# GPIO.net
KiCad netlist of a schematic drawn in Altium Designer
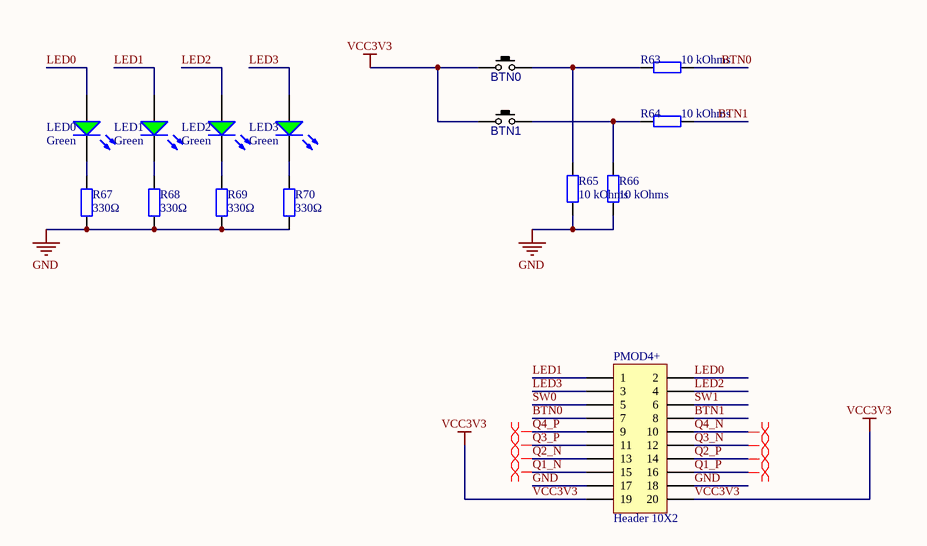
[diagram p0: GPIO.SchDoc]

(export (version "E")
  (design (tool "Eeschema 10.0.6"))
  (components
    (comp (ref "BTN0")
      (value "PUSHBUTTON")
      (footprint "SWPBS_SPST_6X3X5")
      (description "SWITCH, PUSH BUTTON, TACTILE, SMD, SPST, 6X3.5X4.3mm")
      (fields (field (name "MANF") "Panasonic") (field (name "MANF_P#") "EVQ-PNF04M"))
      (libsource (lib "Switch Push Botton") (part "SWPBS_SPST_6X3X4"))
    )
    (comp (ref "BTN1")
      (value "PUSHBUTTON")
      (footprint "SWPBS_SPST_6X3X5")
      (description "SWITCH, PUSH BUTTON, TACTILE, SMD, SPST, 6X3.5X4.3mm")
      (fields (field (name "MANF") "Panasonic") (field (name "MANF_P#") "EVQ-PNF04M"))
      (libsource (lib "Switch Push Botton") (part "SWPBS_SPST_6X3X4"))
    )
    (comp (ref "LED0")
      (value "Green")
      (footprint "0805_LED_S1")
      (description "发光二极管")
      (libsource (lib "LED") (part "0805 翠绿"))
    )
    (comp (ref "LED1")
      (value "Green")
      (footprint "0805_LED_S1")
      (description "发光二极管")
      (libsource (lib "LED") (part "0805 翠绿"))
    )
    (comp (ref "LED2")
      (value "Green")
      (footprint "0805_LED_S1")
      (description "发光二极管")
      (libsource (lib "LED") (part "0805 翠绿"))
    )
    (comp (ref "LED3")
      (value "Green")
      (footprint "0805_LED_S1")
      (description "发光二极管")
      (libsource (lib "LED") (part "0805 翠绿"))
    )
    (comp (ref "PMOD4+")
      (value "Header 10X2")
      (footprint "HDR2X10")
      (description "Header, 10-Pin, Dual row")
      (fields (field (name "PUBLISHER") "Altium Limited"))
      (libsource (lib "Miscellaneous Connectors") (part "Header 10X2"))
    )
    (comp (ref "R63")
      (value "10 kOhms")
      (footprint "RES0402i")
      (description "0402, 10K 1%,  62.5mW, 50V")
      (fields (field (name "PART NUMBER") "CR0402-FX-1002GLF") (field (name "VOLTAGE") "50V"))
      (libsource (lib "") (part "Res_10k_1%_0402_1"))
    )
    (comp (ref "R64")
      (value "10 kOhms")
      (footprint "RES0402i")
      (description "0402, 10K 1%,  62.5mW, 50V")
      (fields (field (name "PART NUMBER") "CR0402-FX-1002GLF") (field (name "VOLTAGE") "50V"))
      (libsource (lib "") (part "Res_10k_1%_0402_1"))
    )
    (comp (ref "R65")
      (value "10 kOhms")
      (footprint "RES0402i")
      (description "0402, 10K 1%,  62.5mW, 50V")
      (fields (field (name "PART NUMBER") "CR0402-FX-1002GLF") (field (name "VOLTAGE") "50V"))
      (libsource (lib "AmpherLib") (part "Res_10k_1%_0402"))
    )
    (comp (ref "R66")
      (value "10 kOhms")
      (footprint "RES0402i")
      (description "0402, 10K 1%,  62.5mW, 50V")
      (fields (field (name "PART NUMBER") "CR0402-FX-1002GLF") (field (name "VOLTAGE") "50V"))
      (libsource (lib "AmpherLib") (part "Res_10k_1%_0402"))
    )
    (comp (ref "R67")
      (value "330Ω")
      (footprint "0805_R")
      (description "贴片电阻")
      (libsource (lib "RES") (part "0805 330Ω (3300) 1%"))
    )
    (comp (ref "R68")
      (value "330Ω")
      (footprint "0805_R")
      (description "贴片电阻")
      (libsource (lib "RES") (part "0805 330Ω (3300) 1%"))
    )
    (comp (ref "R69")
      (value "330Ω")
      (footprint "0805_R")
      (description "贴片电阻")
      (libsource (lib "RES") (part "0805 330Ω (3300) 1%"))
    )
    (comp (ref "R70")
      (value "330Ω")
      (footprint "0805_R")
      (description "贴片电阻")
      (libsource (lib "RES") (part "0805 330Ω (3300) 1%"))
    )
  )
  (nets
    (net (code "1") (name "/BTN0") (class "Default")
      (node (ref "PMOD4+") (pin "7") (pinfunction "7_7") (pintype "passive"))
      (node (ref "R63") (pin "2") (pinfunction "2_2") (pintype "passive"))
    )
    (net (code "2") (name "/BTN1") (class "Default")
      (node (ref "PMOD4+") (pin "8") (pinfunction "8_8") (pintype "passive"))
      (node (ref "R64") (pin "2") (pinfunction "2_2") (pintype "passive"))
    )
    (net (code "3") (name "/LED0") (class "Default")
      (node (ref "LED0") (pin "A") (pinfunction "A_A") (pintype "passive"))
      (node (ref "PMOD4+") (pin "2") (pinfunction "2_2") (pintype "passive"))
    )
    (net (code "4") (name "/LED1") (class "Default")
      (node (ref "LED1") (pin "A") (pinfunction "A_A") (pintype "passive"))
      (node (ref "PMOD4+") (pin "1") (pinfunction "1_1") (pintype "passive"))
    )
    (net (code "5") (name "/LED2") (class "Default")
      (node (ref "LED2") (pin "A") (pinfunction "A_A") (pintype "passive"))
      (node (ref "PMOD4+") (pin "4") (pinfunction "4_4") (pintype "passive"))
    )
    (net (code "6") (name "/LED3") (class "Default")
      (node (ref "LED3") (pin "A") (pinfunction "A_A") (pintype "passive"))
      (node (ref "PMOD4+") (pin "3") (pinfunction "3_3") (pintype "passive"))
    )
    (net (code "7") (name "/Q1_N") (class "Default")
      (node (ref "PMOD4+") (pin "15") (pinfunction "15_15") (pintype "passive"))
    )
    (net (code "8") (name "/Q1_P") (class "Default")
      (node (ref "PMOD4+") (pin "16") (pinfunction "16_16") (pintype "passive"))
    )
    (net (code "9") (name "/Q2_N") (class "Default")
      (node (ref "PMOD4+") (pin "13") (pinfunction "13_13") (pintype "passive"))
    )
    (net (code "10") (name "/Q2_P") (class "Default")
      (node (ref "PMOD4+") (pin "14") (pinfunction "14_14") (pintype "passive"))
    )
    (net (code "11") (name "/Q3_N") (class "Default")
      (node (ref "PMOD4+") (pin "12") (pinfunction "12_12") (pintype "passive"))
    )
    (net (code "12") (name "/Q3_P") (class "Default")
      (node (ref "PMOD4+") (pin "11") (pinfunction "11_11") (pintype "passive"))
    )
    (net (code "13") (name "/Q4_N") (class "Default")
      (node (ref "PMOD4+") (pin "10") (pinfunction "10_10") (pintype "passive"))
    )
    (net (code "14") (name "/Q4_P") (class "Default")
      (node (ref "PMOD4+") (pin "9") (pinfunction "9_9") (pintype "passive"))
    )
    (net (code "15") (name "/SW0") (class "Default")
      (node (ref "PMOD4+") (pin "5") (pinfunction "5_5") (pintype "passive"))
    )
    (net (code "16") (name "/SW1") (class "Default")
      (node (ref "PMOD4+") (pin "6") (pinfunction "6_6") (pintype "passive"))
    )
    (net (code "17") (name "GND") (class "Default")
      (node (ref "PMOD4+") (pin "17") (pinfunction "17_17") (pintype "passive"))
      (node (ref "PMOD4+") (pin "18") (pinfunction "18_18") (pintype "passive"))
      (node (ref "R65") (pin "1") (pinfunction "1_1") (pintype "passive"))
      (node (ref "R66") (pin "1") (pinfunction "1_1") (pintype "passive"))
      (node (ref "R67") (pin "1") (pinfunction "1_1") (pintype "passive"))
      (node (ref "R68") (pin "1") (pinfunction "1_1") (pintype "passive"))
      (node (ref "R69") (pin "1") (pinfunction "1_1") (pintype "passive"))
      (node (ref "R70") (pin "1") (pinfunction "1_1") (pintype "passive"))
    )
    (net (code "18") (name "Net-(BTN0-P3)") (class "Default")
      (node (ref "BTN0") (pin "2") (pinfunction "P3_2") (pintype "passive"))
      (node (ref "R63") (pin "1") (pinfunction "1_1") (pintype "passive"))
      (node (ref "R65") (pin "2") (pinfunction "2_2") (pintype "passive"))
    )
    (net (code "19") (name "Net-(BTN1-P3)") (class "Default")
      (node (ref "BTN1") (pin "2") (pinfunction "P3_2") (pintype "passive"))
      (node (ref "R64") (pin "1") (pinfunction "1_1") (pintype "passive"))
      (node (ref "R66") (pin "2") (pinfunction "2_2") (pintype "passive"))
    )
    (net (code "20") (name "Net-(LED0-PadK)") (class "Default")
      (node (ref "LED0") (pin "K") (pinfunction "K_K") (pintype "passive"))
      (node (ref "R67") (pin "2") (pinfunction "2_2") (pintype "passive"))
    )
    (net (code "21") (name "Net-(LED1-PadK)") (class "Default")
      (node (ref "LED1") (pin "K") (pinfunction "K_K") (pintype "passive"))
      (node (ref "R68") (pin "2") (pinfunction "2_2") (pintype "passive"))
    )
    (net (code "22") (name "Net-(LED2-PadK)") (class "Default")
      (node (ref "LED2") (pin "K") (pinfunction "K_K") (pintype "passive"))
      (node (ref "R69") (pin "2") (pinfunction "2_2") (pintype "passive"))
    )
    (net (code "23") (name "Net-(LED3-PadK)") (class "Default")
      (node (ref "LED3") (pin "K") (pinfunction "K_K") (pintype "passive"))
      (node (ref "R70") (pin "2") (pinfunction "2_2") (pintype "passive"))
    )
    (net (code "24") (name "VCC3V3") (class "Default")
      (node (ref "BTN0") (pin "1") (pinfunction "P1_1") (pintype "passive"))
      (node (ref "BTN1") (pin "1") (pinfunction "P1_1") (pintype "passive"))
      (node (ref "PMOD4+") (pin "19") (pinfunction "19_19") (pintype "passive"))
      (node (ref "PMOD4+") (pin "20") (pinfunction "20_20") (pintype "passive"))
    )
  )
)
